# mini3216_V2_0.net
KiCad netlist of a schematic drawn in Altium Designer
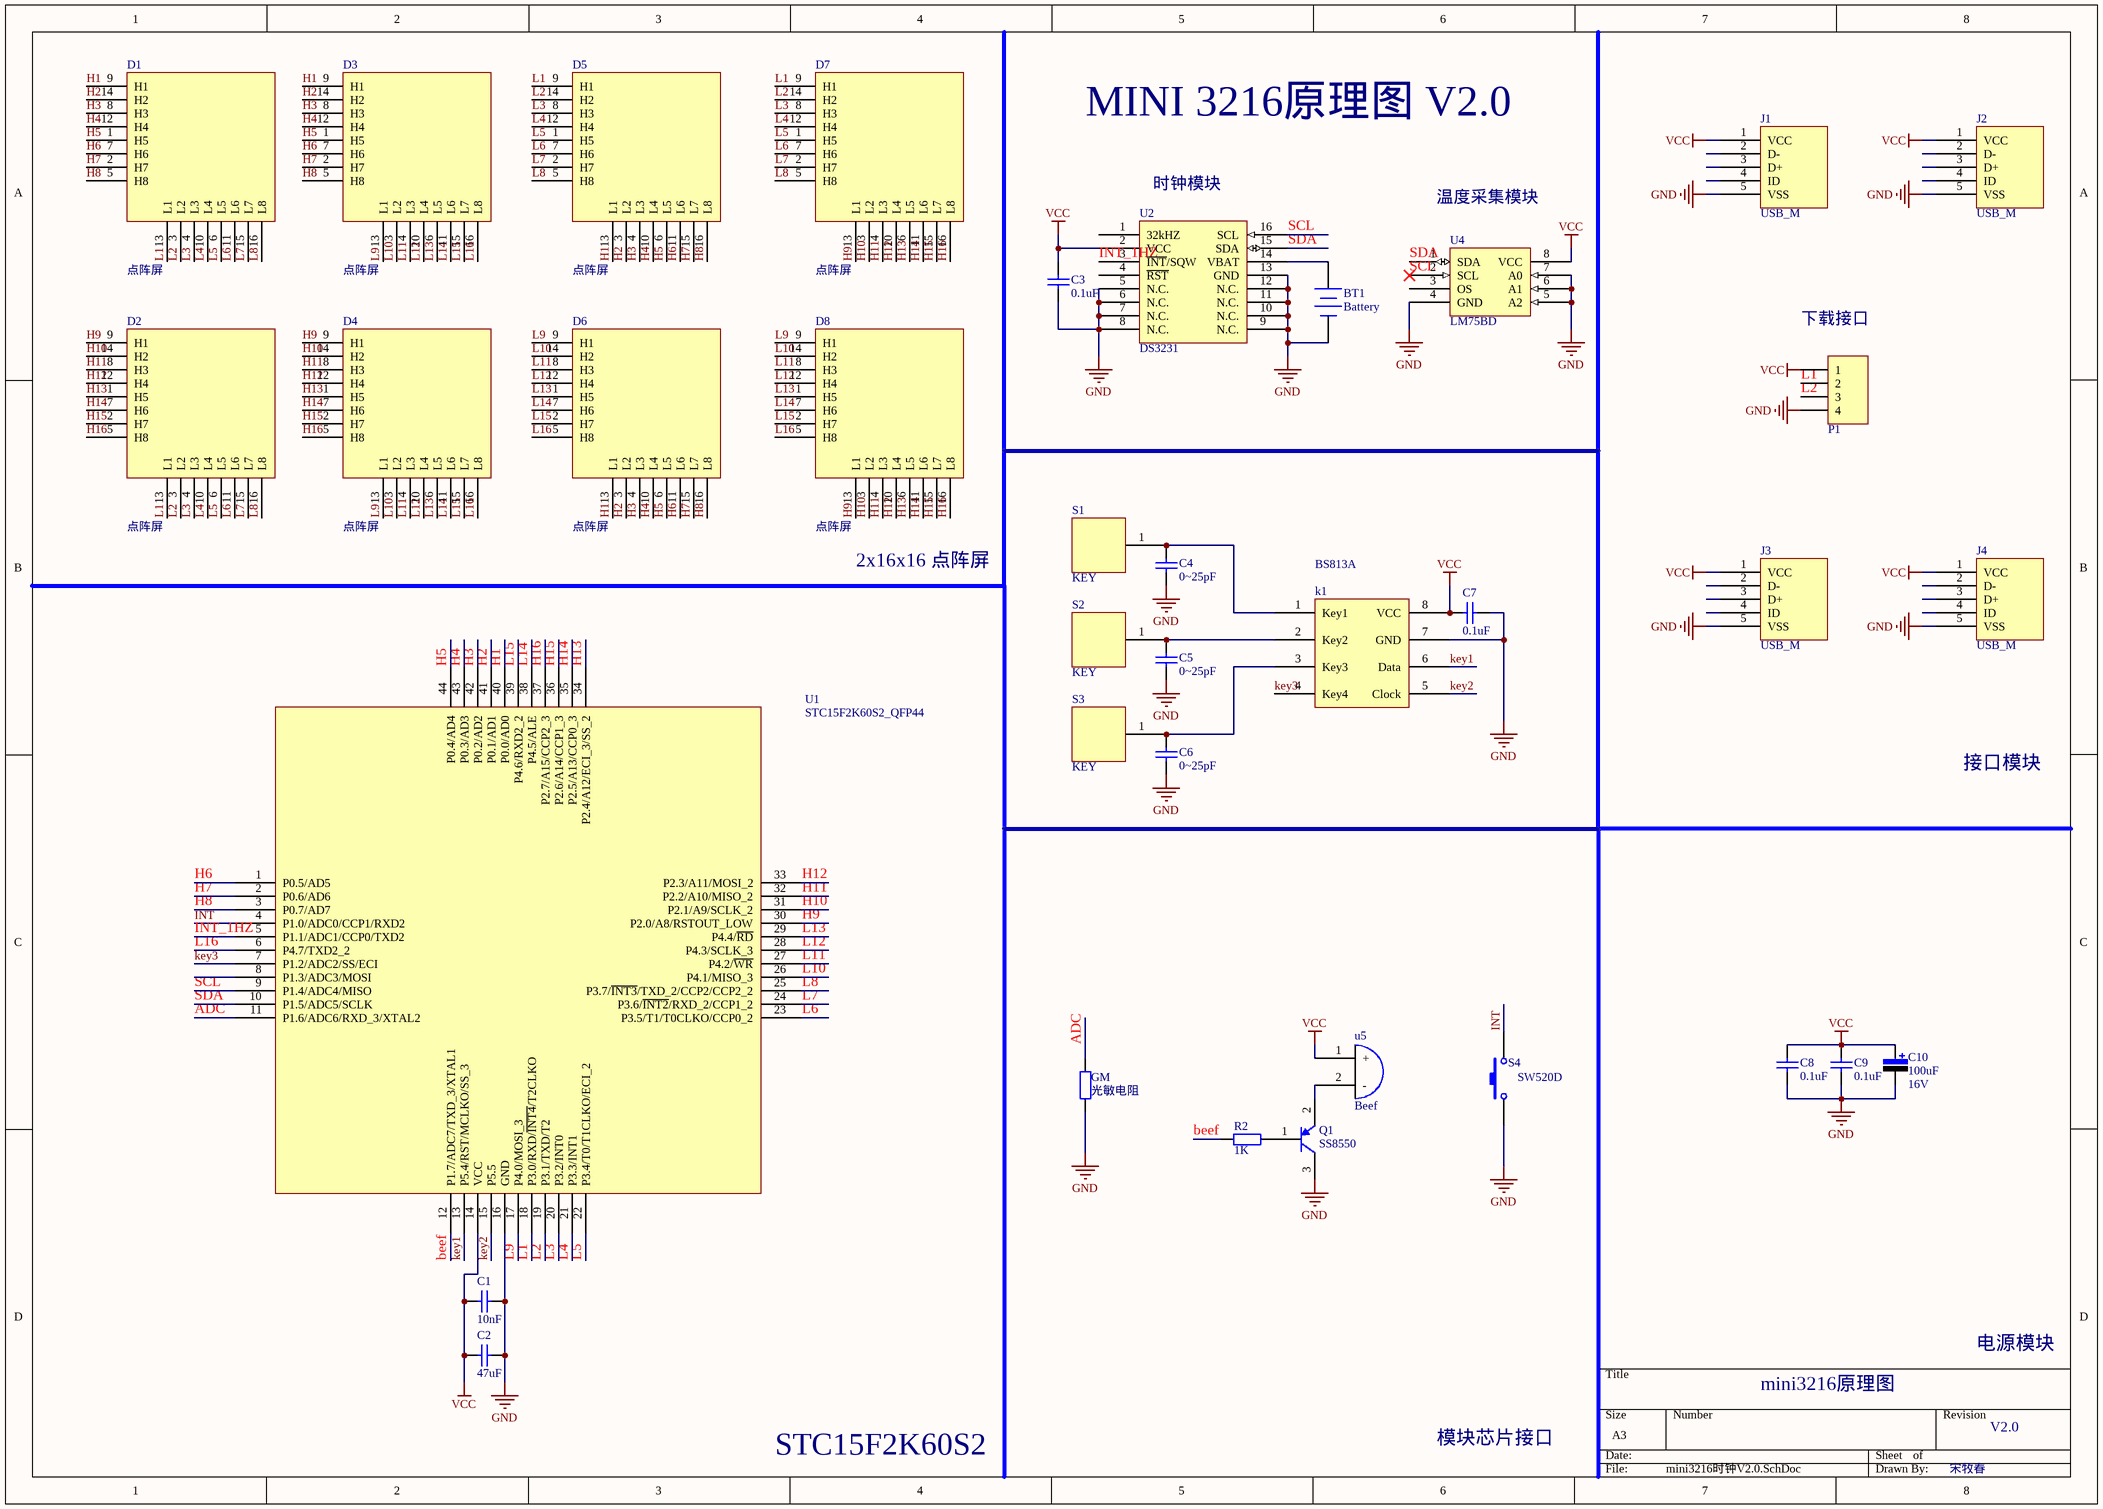
[diagram p0: mini3216时钟V2.0.SchDoc]

(export (version "E")
  (design (tool "Eeschema 10.0.6"))
  (components
    (comp (ref "BT1")
      (value "Battery")
      (footprint "CR1220电池座")
      (description "备份电池")
      (fields (field (name "PUBLISHER") "Altium Limited"))
      (libsource (lib "SMC_Devices") (part "Battery"))
    )
    (comp (ref "C1")
      (value "10nF")
      (footprint "C-RAD-0805")
      (description "无极性电容")
      (fields (field (name "Comment") "Cap") (field (name "PUBLISHER") "Altium Limited"))
      (libsource (lib "SMC_Devices") (part "Cap"))
    )
    (comp (ref "C2")
      (value "47uF")
      (footprint "1206(3216)")
      (description "无极性电容")
      (fields (field (name "Comment") "Cap") (field (name "PUBLISHER") "Altium Limited"))
      (libsource (lib "SMC_Devices") (part "Cap"))
    )
    (comp (ref "C3")
      (value "0.1uF")
      (footprint "C-RAD-0805")
      (description "无极性电容")
      (fields (field (name "Comment") "Cap") (field (name "PUBLISHER") "Altium Limited"))
      (libsource (lib "SMC_Devices") (part "Cap"))
    )
    (comp (ref "C4")
      (value "0~25pF")
      (footprint "C-RAD-0805")
      (description "无极性电容")
      (fields (field (name "Comment") "Cap") (field (name "PUBLISHER") "Altium Limited"))
      (libsource (lib "SMC_Devices") (part "Cap"))
    )
    (comp (ref "C5")
      (value "0~25pF")
      (footprint "C-RAD-0805")
      (description "无极性电容")
      (fields (field (name "Comment") "Cap") (field (name "PUBLISHER") "Altium Limited"))
      (libsource (lib "SMC_Devices") (part "Cap"))
    )
    (comp (ref "C6")
      (value "0~25pF")
      (footprint "C-RAD-0805")
      (description "无极性电容")
      (fields (field (name "Comment") "Cap") (field (name "PUBLISHER") "Altium Limited"))
      (libsource (lib "SMC_Devices") (part "Cap"))
    )
    (comp (ref "C7")
      (value "0.1uF")
      (footprint "C-RAD-0805")
      (description "无极性电容")
      (fields (field (name "Comment") "Cap") (field (name "PUBLISHER") "Altium Limited"))
      (libsource (lib "SMC_Devices") (part "Cap"))
    )
    (comp (ref "C8")
      (value "0.1uF")
      (footprint "C-RAD-0805")
      (description "无极性电容")
      (fields (field (name "Comment") "Cap") (field (name "PUBLISHER") "Altium Limited"))
      (libsource (lib "SMC_Devices") (part "Cap"))
    )
    (comp (ref "C9")
      (value "0.1uF")
      (footprint "C-RAD-0805")
      (description "无极性电容")
      (fields (field (name "Comment") "Cap") (field (name "PUBLISHER") "Altium Limited"))
      (libsource (lib "SMC_Devices") (part "Cap"))
    )
    (comp (ref "C10")
      (value "100uF")
      (footprint "CAP-3528")
      (description "极性电解电容")
      (fields
        (field (name "VOL") "16V")
        (field (name "Comment") "Cap Pol")
        (field (name "PUBLISHER") "Altium Limited")
      )
      (libsource (lib "SMC_Devices") (part "Cap Pol"))
    )
    (comp (ref "D1") (value "点阵屏") (footprint "LED_点阵1088") (libsource (lib "mini3216") (part "LED_点阵屏8x8")))
    (comp (ref "D2") (value "点阵屏") (footprint "LED_点阵1088") (libsource (lib "mini3216") (part "LED_点阵屏8x8")))
    (comp (ref "D3") (value "点阵屏") (footprint "LED_点阵1088") (libsource (lib "mini3216") (part "LED_点阵屏8x8")))
    (comp (ref "D4") (value "点阵屏") (footprint "LED_点阵1088") (libsource (lib "mini3216") (part "LED_点阵屏8x8")))
    (comp (ref "D5") (value "点阵屏") (footprint "LED_点阵1088") (libsource (lib "mini3216") (part "LED_点阵屏8x8")))
    (comp (ref "D6") (value "点阵屏") (footprint "LED_点阵1088") (libsource (lib "mini3216") (part "LED_点阵屏8x8")))
    (comp (ref "D7") (value "点阵屏") (footprint "LED_点阵1088") (libsource (lib "mini3216") (part "LED_点阵屏8x8")))
    (comp (ref "D8") (value "点阵屏") (footprint "LED_点阵1088") (libsource (lib "mini3216") (part "LED_点阵屏8x8")))
    (comp (ref "GM")
      (value "光敏电阻")
      (footprint "光敏电阻")
      (description "贴片电阻")
      (fields (field (name "Comment") "Res1") (field (name "PUBLISHER") "Altium Limited"))
      (libsource (lib "SMC_Devices") (part "Res1"))
    )
    (comp (ref "J1")
      (value "USB_M")
      (footprint "USB_MICRO")
      (description "MicroUSB接口")
      (libsource (lib "SMC_Devices") (part "USB_M"))
    )
    (comp (ref "J2")
      (value "USB_M")
      (footprint "USB_MICRO")
      (description "MicroUSB接口")
      (libsource (lib "SMC_Devices") (part "USB_M"))
    )
    (comp (ref "J3")
      (value "USB_M")
      (footprint "USB_MICRO")
      (description "MicroUSB接口")
      (libsource (lib "SMC_Devices") (part "USB_M"))
    )
    (comp (ref "J4")
      (value "USB_M")
      (footprint "USB_MICRO")
      (description "MicroUSB接口")
      (libsource (lib "SMC_Devices") (part "USB_M"))
    )
    (comp (ref "k1") (value "BS813A") (footprint "SOP8") (libsource (lib "mini3216") (part "BS814A-2触摸按键")))
    (comp (ref "P1")
      (value "Header 4")
      (footprint "HDR4X1_A")
      (description "接插件")
      (fields (field (name "PUBLISHER") "Altium Limited"))
      (libsource (lib "SMC_Devices") (part "Header 4"))
    )
    (comp (ref "Q1")
      (value "SS8550")
      (footprint "SOT-23")
      (description "PNP贴片三极管")
      (fields (field (name "PUBLISHER") "Altium Limited"))
      (libsource (lib "SMC_Devices") (part "SS8550"))
    )
    (comp (ref "R2")
      (value "1K")
      (footprint "0805-1")
      (description "贴片电阻")
      (fields (field (name "Comment") "Res1") (field (name "PUBLISHER") "Altium Limited"))
      (libsource (lib "") (part "Res1_1"))
    )
    (comp (ref "S1") (value "KEY") (footprint "KEY1") (libsource (lib "mini3216") (part "TouchKEY")))
    (comp (ref "S2") (value "KEY") (footprint "KEY2") (libsource (lib "mini3216") (part "TouchKEY")))
    (comp (ref "S3") (value "KEY") (footprint "KEY3") (libsource (lib "mini3216") (part "TouchKEY")))
    (comp (ref "S4")
      (value "SW520D")
      (footprint "SW_PB2_A1")
      (description "微动开关")
      (fields (field (name "PUBLISHER") "Altium Limited"))
      (libsource (lib "SMC_Devices") (part "SW-PB"))
    )
    (comp (ref "U1")
      (value "STC15F2K60S2_QFP44")
      (footprint "LQFP44")
      (libsource (lib "stcmcu_altium_lib") (part "STC15F2K60S2_QFP44"))
    )
    (comp (ref "U2") (value "DS3231") (footprint "DS3231SN") (libsource (lib "mini3216") (part "DS3231")))
    (comp (ref "U4") (value "LM75BD") (footprint "LM75BD") (libsource (lib "mini3216") (part "LM75BD")))
    (comp (ref "u5") (value "Beef") (footprint "BEEF") (libsource (lib "mini3216") (part "Beef")))
  )
  (nets
    (net (code "1") (name "/ADC") (class "Default")
      (node (ref "GM") (pin "2") (pinfunction "2_2") (pintype "passive"))
      (node (ref "U1") (pin "11") (pinfunction "P1.6/ADC6/RXD_3/XTAL2_11") (pintype "passive"))
    )
    (net (code "2") (name "/H1") (class "Default")
      (node (ref "D1") (pin "9") (pinfunction "H1_9") (pintype "passive"))
      (node (ref "D3") (pin "9") (pinfunction "H1_9") (pintype "passive"))
      (node (ref "D5") (pin "13") (pinfunction "L1_13") (pintype "passive"))
      (node (ref "D6") (pin "13") (pinfunction "L1_13") (pintype "passive"))
      (node (ref "U1") (pin "40") (pinfunction "P0.0/AD0_40") (pintype "passive"))
    )
    (net (code "3") (name "/H2") (class "Default")
      (node (ref "D1") (pin "14") (pinfunction "H2_14") (pintype "passive"))
      (node (ref "D3") (pin "14") (pinfunction "H2_14") (pintype "passive"))
      (node (ref "D5") (pin "3") (pinfunction "L2_3") (pintype "passive"))
      (node (ref "D6") (pin "3") (pinfunction "L2_3") (pintype "passive"))
      (node (ref "U1") (pin "41") (pinfunction "P0.1/AD1_41") (pintype "passive"))
    )
    (net (code "4") (name "/H3") (class "Default")
      (node (ref "D1") (pin "8") (pinfunction "H3_8") (pintype "passive"))
      (node (ref "D3") (pin "8") (pinfunction "H3_8") (pintype "passive"))
      (node (ref "D5") (pin "4") (pinfunction "L3_4") (pintype "passive"))
      (node (ref "D6") (pin "4") (pinfunction "L3_4") (pintype "passive"))
      (node (ref "U1") (pin "42") (pinfunction "P0.2/AD2_42") (pintype "passive"))
    )
    (net (code "5") (name "/H4") (class "Default")
      (node (ref "D1") (pin "12") (pinfunction "H4_12") (pintype "passive"))
      (node (ref "D3") (pin "12") (pinfunction "H4_12") (pintype "passive"))
      (node (ref "D5") (pin "10") (pinfunction "L4_10") (pintype "passive"))
      (node (ref "D6") (pin "10") (pinfunction "L4_10") (pintype "passive"))
      (node (ref "U1") (pin "43") (pinfunction "P0.3/AD3_43") (pintype "passive"))
    )
    (net (code "6") (name "/H5") (class "Default")
      (node (ref "D1") (pin "1") (pinfunction "H5_1") (pintype "passive"))
      (node (ref "D3") (pin "1") (pinfunction "H5_1") (pintype "passive"))
      (node (ref "D5") (pin "6") (pinfunction "L5_6") (pintype "passive"))
      (node (ref "D6") (pin "6") (pinfunction "L5_6") (pintype "passive"))
      (node (ref "U1") (pin "44") (pinfunction "P0.4/AD4_44") (pintype "passive"))
    )
    (net (code "7") (name "/H6") (class "Default")
      (node (ref "D1") (pin "7") (pinfunction "H6_7") (pintype "passive"))
      (node (ref "D3") (pin "7") (pinfunction "H6_7") (pintype "passive"))
      (node (ref "D5") (pin "11") (pinfunction "L6_11") (pintype "passive"))
      (node (ref "D6") (pin "11") (pinfunction "L6_11") (pintype "passive"))
      (node (ref "U1") (pin "1") (pinfunction "P0.5/AD5_1") (pintype "passive"))
    )
    (net (code "8") (name "/H7") (class "Default")
      (node (ref "D1") (pin "2") (pinfunction "H7_2") (pintype "passive"))
      (node (ref "D3") (pin "2") (pinfunction "H7_2") (pintype "passive"))
      (node (ref "D5") (pin "15") (pinfunction "L7_15") (pintype "passive"))
      (node (ref "D6") (pin "15") (pinfunction "L7_15") (pintype "passive"))
      (node (ref "U1") (pin "2") (pinfunction "P0.6/AD6_2") (pintype "passive"))
    )
    (net (code "9") (name "/H8") (class "Default")
      (node (ref "D1") (pin "5") (pinfunction "H8_5") (pintype "passive"))
      (node (ref "D3") (pin "5") (pinfunction "H8_5") (pintype "passive"))
      (node (ref "D5") (pin "16") (pinfunction "L8_16") (pintype "passive"))
      (node (ref "D6") (pin "16") (pinfunction "L8_16") (pintype "passive"))
      (node (ref "U1") (pin "3") (pinfunction "P0.7/AD7_3") (pintype "passive"))
    )
    (net (code "10") (name "/H9") (class "Default")
      (node (ref "D2") (pin "9") (pinfunction "H1_9") (pintype "passive"))
      (node (ref "D4") (pin "9") (pinfunction "H1_9") (pintype "passive"))
      (node (ref "D7") (pin "13") (pinfunction "L1_13") (pintype "passive"))
      (node (ref "D8") (pin "13") (pinfunction "L1_13") (pintype "passive"))
      (node (ref "U1") (pin "30") (pinfunction "P2.0/A8/RSTOUT_LOW_30") (pintype "passive"))
    )
    (net (code "11") (name "/H10") (class "Default")
      (node (ref "D2") (pin "14") (pinfunction "H2_14") (pintype "passive"))
      (node (ref "D4") (pin "14") (pinfunction "H2_14") (pintype "passive"))
      (node (ref "D7") (pin "3") (pinfunction "L2_3") (pintype "passive"))
      (node (ref "D8") (pin "3") (pinfunction "L2_3") (pintype "passive"))
      (node (ref "U1") (pin "31") (pinfunction "P2.1/A9/SCLK_2_31") (pintype "passive"))
    )
    (net (code "12") (name "/H11") (class "Default")
      (node (ref "D2") (pin "8") (pinfunction "H3_8") (pintype "passive"))
      (node (ref "D4") (pin "8") (pinfunction "H3_8") (pintype "passive"))
      (node (ref "D7") (pin "4") (pinfunction "L3_4") (pintype "passive"))
      (node (ref "D8") (pin "4") (pinfunction "L3_4") (pintype "passive"))
      (node (ref "U1") (pin "32") (pinfunction "P2.2/A10/MISO_2_32") (pintype "passive"))
    )
    (net (code "13") (name "/H12") (class "Default")
      (node (ref "D2") (pin "12") (pinfunction "H4_12") (pintype "passive"))
      (node (ref "D4") (pin "12") (pinfunction "H4_12") (pintype "passive"))
      (node (ref "D7") (pin "10") (pinfunction "L4_10") (pintype "passive"))
      (node (ref "D8") (pin "10") (pinfunction "L4_10") (pintype "passive"))
      (node (ref "U1") (pin "33") (pinfunction "P2.3/A11/MOSI_2_33") (pintype "passive"))
    )
    (net (code "14") (name "/H13") (class "Default")
      (node (ref "D2") (pin "1") (pinfunction "H5_1") (pintype "passive"))
      (node (ref "D4") (pin "1") (pinfunction "H5_1") (pintype "passive"))
      (node (ref "D7") (pin "6") (pinfunction "L5_6") (pintype "passive"))
      (node (ref "D8") (pin "6") (pinfunction "L5_6") (pintype "passive"))
      (node (ref "U1") (pin "34") (pinfunction "P2.4/A12/ECI_3/SS_2_34") (pintype "passive"))
    )
    (net (code "15") (name "/H14") (class "Default")
      (node (ref "D2") (pin "7") (pinfunction "H6_7") (pintype "passive"))
      (node (ref "D4") (pin "7") (pinfunction "H6_7") (pintype "passive"))
      (node (ref "D7") (pin "11") (pinfunction "L6_11") (pintype "passive"))
      (node (ref "D8") (pin "11") (pinfunction "L6_11") (pintype "passive"))
      (node (ref "U1") (pin "35") (pinfunction "P2.5/A13/CCP0_3_35") (pintype "passive"))
    )
    (net (code "16") (name "/H15") (class "Default")
      (node (ref "D2") (pin "2") (pinfunction "H7_2") (pintype "passive"))
      (node (ref "D4") (pin "2") (pinfunction "H7_2") (pintype "passive"))
      (node (ref "D7") (pin "15") (pinfunction "L7_15") (pintype "passive"))
      (node (ref "D8") (pin "15") (pinfunction "L7_15") (pintype "passive"))
      (node (ref "U1") (pin "36") (pinfunction "P2.6/A14/CCP1_3_36") (pintype "passive"))
    )
    (net (code "17") (name "/H16") (class "Default")
      (node (ref "D2") (pin "5") (pinfunction "H8_5") (pintype "passive"))
      (node (ref "D4") (pin "5") (pinfunction "H8_5") (pintype "passive"))
      (node (ref "D7") (pin "16") (pinfunction "L8_16") (pintype "passive"))
      (node (ref "D8") (pin "16") (pinfunction "L8_16") (pintype "passive"))
      (node (ref "U1") (pin "37") (pinfunction "P2.7/A15/CCP2_3_37") (pintype "passive"))
    )
    (net (code "18") (name "/INT") (class "Default")
      (node (ref "S4") (pin "2") (pinfunction "2_2") (pintype "passive"))
      (node (ref "U1") (pin "4") (pinfunction "P1.0/ADC0/CCP1/RXD2_4") (pintype "passive"))
    )
    (net (code "19") (name "/INT_1HZ") (class "Default")
      (node (ref "U1") (pin "5") (pinfunction "P1.1/ADC1/CCP0/TXD2_5") (pintype "passive"))
      (node (ref "U2") (pin "3") (pinfunction "~{INT}/SQW_3") (pintype "open_collector"))
    )
    (net (code "20") (name "/L1") (class "Default")
      (node (ref "D1") (pin "13") (pinfunction "L1_13") (pintype "passive"))
      (node (ref "D2") (pin "13") (pinfunction "L1_13") (pintype "passive"))
      (node (ref "D5") (pin "9") (pinfunction "H1_9") (pintype "passive"))
      (node (ref "D7") (pin "9") (pinfunction "H1_9") (pintype "passive"))
      (node (ref "P1") (pin "2") (pinfunction "2_2") (pintype "passive"))
      (node (ref "U1") (pin "18") (pinfunction "P3.0/RXD/~{INT4}/T2CLKO_18") (pintype "passive"))
    )
    (net (code "21") (name "/L2") (class "Default")
      (node (ref "D1") (pin "3") (pinfunction "L2_3") (pintype "passive"))
      (node (ref "D2") (pin "3") (pinfunction "L2_3") (pintype "passive"))
      (node (ref "D5") (pin "14") (pinfunction "H2_14") (pintype "passive"))
      (node (ref "D7") (pin "14") (pinfunction "H2_14") (pintype "passive"))
      (node (ref "P1") (pin "3") (pinfunction "3_3") (pintype "passive"))
      (node (ref "U1") (pin "19") (pinfunction "P3.1/TXD/T2_19") (pintype "passive"))
    )
    (net (code "22") (name "/L3") (class "Default")
      (node (ref "D1") (pin "4") (pinfunction "L3_4") (pintype "passive"))
      (node (ref "D2") (pin "4") (pinfunction "L3_4") (pintype "passive"))
      (node (ref "D5") (pin "8") (pinfunction "H3_8") (pintype "passive"))
      (node (ref "D7") (pin "8") (pinfunction "H3_8") (pintype "passive"))
      (node (ref "U1") (pin "20") (pinfunction "P3.2/INT0_20") (pintype "passive"))
    )
    (net (code "23") (name "/L4") (class "Default")
      (node (ref "D1") (pin "10") (pinfunction "L4_10") (pintype "passive"))
      (node (ref "D2") (pin "10") (pinfunction "L4_10") (pintype "passive"))
      (node (ref "D5") (pin "12") (pinfunction "H4_12") (pintype "passive"))
      (node (ref "D7") (pin "12") (pinfunction "H4_12") (pintype "passive"))
      (node (ref "U1") (pin "21") (pinfunction "P3.3/INT1_21") (pintype "passive"))
    )
    (net (code "24") (name "/L5") (class "Default")
      (node (ref "D1") (pin "6") (pinfunction "L5_6") (pintype "passive"))
      (node (ref "D2") (pin "6") (pinfunction "L5_6") (pintype "passive"))
      (node (ref "D5") (pin "1") (pinfunction "H5_1") (pintype "passive"))
      (node (ref "D7") (pin "1") (pinfunction "H5_1") (pintype "passive"))
      (node (ref "U1") (pin "22") (pinfunction "P3.4/T0/T1CLKO/ECI_2_22") (pintype "passive"))
    )
    (net (code "25") (name "/L6") (class "Default")
      (node (ref "D1") (pin "11") (pinfunction "L6_11") (pintype "passive"))
      (node (ref "D2") (pin "11") (pinfunction "L6_11") (pintype "passive"))
      (node (ref "D5") (pin "7") (pinfunction "H6_7") (pintype "passive"))
      (node (ref "D7") (pin "7") (pinfunction "H6_7") (pintype "passive"))
      (node (ref "U1") (pin "23") (pinfunction "P3.5/T1/T0CLKO/CCP0_2_23") (pintype "passive"))
    )
    (net (code "26") (name "/L7") (class "Default")
      (node (ref "D1") (pin "15") (pinfunction "L7_15") (pintype "passive"))
      (node (ref "D2") (pin "15") (pinfunction "L7_15") (pintype "passive"))
      (node (ref "D5") (pin "2") (pinfunction "H7_2") (pintype "passive"))
      (node (ref "D7") (pin "2") (pinfunction "H7_2") (pintype "passive"))
      (node (ref "U1") (pin "24") (pinfunction "P3.6/~{INT2}/RXD_2/CCP1_2_24") (pintype "passive"))
    )
    (net (code "27") (name "/L8") (class "Default")
      (node (ref "D1") (pin "16") (pinfunction "L8_16") (pintype "passive"))
      (node (ref "D2") (pin "16") (pinfunction "L8_16") (pintype "passive"))
      (node (ref "D5") (pin "5") (pinfunction "H8_5") (pintype "passive"))
      (node (ref "D7") (pin "5") (pinfunction "H8_5") (pintype "passive"))
      (node (ref "U1") (pin "25") (pinfunction "P3.7/~{INT3}/TXD_2/CCP2/CCP2_2_25") (pintype "passive"))
    )
    (net (code "28") (name "/L9") (class "Default")
      (node (ref "D3") (pin "13") (pinfunction "L1_13") (pintype "passive"))
      (node (ref "D4") (pin "13") (pinfunction "L1_13") (pintype "passive"))
      (node (ref "D6") (pin "9") (pinfunction "H1_9") (pintype "passive"))
      (node (ref "D8") (pin "9") (pinfunction "H1_9") (pintype "passive"))
      (node (ref "U1") (pin "17") (pinfunction "P4.0/MOSI_3_17") (pintype "passive"))
    )
    (net (code "29") (name "/L10") (class "Default")
      (node (ref "D3") (pin "3") (pinfunction "L2_3") (pintype "passive"))
      (node (ref "D4") (pin "3") (pinfunction "L2_3") (pintype "passive"))
      (node (ref "D6") (pin "14") (pinfunction "H2_14") (pintype "passive"))
      (node (ref "D8") (pin "14") (pinfunction "H2_14") (pintype "passive"))
      (node (ref "U1") (pin "26") (pinfunction "P4.1/MISO_3_26") (pintype "passive"))
    )
    (net (code "30") (name "/L11") (class "Default")
      (node (ref "D3") (pin "4") (pinfunction "L3_4") (pintype "passive"))
      (node (ref "D4") (pin "4") (pinfunction "L3_4") (pintype "passive"))
      (node (ref "D6") (pin "8") (pinfunction "H3_8") (pintype "passive"))
      (node (ref "D8") (pin "8") (pinfunction "H3_8") (pintype "passive"))
      (node (ref "U1") (pin "27") (pinfunction "P4.2/~{WR}_27") (pintype "passive"))
    )
    (net (code "31") (name "/L12") (class "Default")
      (node (ref "D3") (pin "10") (pinfunction "L4_10") (pintype "passive"))
      (node (ref "D4") (pin "10") (pinfunction "L4_10") (pintype "passive"))
      (node (ref "D6") (pin "12") (pinfunction "H4_12") (pintype "passive"))
      (node (ref "D8") (pin "12") (pinfunction "H4_12") (pintype "passive"))
      (node (ref "U1") (pin "28") (pinfunction "P4.3/SCLK_3_28") (pintype "passive"))
    )
    (net (code "32") (name "/L13") (class "Default")
      (node (ref "D3") (pin "6") (pinfunction "L5_6") (pintype "passive"))
      (node (ref "D4") (pin "6") (pinfunction "L5_6") (pintype "passive"))
      (node (ref "D6") (pin "1") (pinfunction "H5_1") (pintype "passive"))
      (node (ref "D8") (pin "1") (pinfunction "H5_1") (pintype "passive"))
      (node (ref "U1") (pin "29") (pinfunction "P4.4/~{RD}_29") (pintype "passive"))
    )
    (net (code "33") (name "/L14") (class "Default")
      (node (ref "D3") (pin "11") (pinfunction "L6_11") (pintype "passive"))
      (node (ref "D4") (pin "11") (pinfunction "L6_11") (pintype "passive"))
      (node (ref "D6") (pin "7") (pinfunction "H6_7") (pintype "passive"))
      (node (ref "D8") (pin "7") (pinfunction "H6_7") (pintype "passive"))
      (node (ref "U1") (pin "38") (pinfunction "P4.5/ALE_38") (pintype "passive"))
    )
    (net (code "34") (name "/L15") (class "Default")
      (node (ref "D3") (pin "15") (pinfunction "L7_15") (pintype "passive"))
      (node (ref "D4") (pin "15") (pinfunction "L7_15") (pintype "passive"))
      (node (ref "D6") (pin "2") (pinfunction "H7_2") (pintype "passive"))
      (node (ref "D8") (pin "2") (pinfunction "H7_2") (pintype "passive"))
      (node (ref "U1") (pin "39") (pinfunction "P4.6/RXD2_2_39") (pintype "passive"))
    )
    (net (code "35") (name "/L16") (class "Default")
      (node (ref "D3") (pin "16") (pinfunction "L8_16") (pintype "passive"))
      (node (ref "D4") (pin "16") (pinfunction "L8_16") (pintype "passive"))
      (node (ref "D6") (pin "5") (pinfunction "H8_5") (pintype "passive"))
      (node (ref "D8") (pin "5") (pinfunction "H8_5") (pintype "passive"))
      (node (ref "U1") (pin "6") (pinfunction "P4.7/TXD2_2_6") (pintype "passive"))
    )
    (net (code "36") (name "/SCL") (class "Default")
      (node (ref "U1") (pin "9") (pinfunction "P1.4/ADC4/MISO_9") (pintype "passive"))
      (node (ref "U2") (pin "16") (pinfunction "SCL_16") (pintype "input"))
      (node (ref "U4") (pin "2") (pinfunction "SCL_2") (pintype "input"))
    )
    (net (code "37") (name "/SDA") (class "Default")
      (node (ref "U1") (pin "10") (pinfunction "P1.5/ADC5/SCLK_10") (pintype "passive"))
      (node (ref "U2") (pin "15") (pinfunction "SDA_15") (pintype "bidirectional"))
      (node (ref "U4") (pin "1") (pinfunction "SDA_1") (pintype "bidirectional"))
    )
    (net (code "38") (name "/beef") (class "Default")
      (node (ref "R2") (pin "1") (pinfunction "1_1") (pintype "passive"))
      (node (ref "U1") (pin "12") (pinfunction "P1.7/ADC7/TXD_3/XTAL1_12") (pintype "passive"))
    )
    (net (code "39") (name "/key1") (class "Default")
      (node (ref "U1") (pin "13") (pinfunction "P5.4/RST/MCLKO/SS_3_13") (pintype "passive"))
      (node (ref "k1") (pin "6") (pinfunction "Data_6") (pintype "passive"))
    )
    (net (code "40") (name "/key2") (class "Default")
      (node (ref "U1") (pin "15") (pinfunction "P5.5_15") (pintype "passive"))
      (node (ref "k1") (pin "5") (pinfunction "Clock_5") (pintype "passive"))
    )
    (net (code "41") (name "/key3") (class "Default")
      (node (ref "U1") (pin "7") (pinfunction "P1.2/ADC2/SS/ECI_7") (pintype "passive"))
      (node (ref "k1") (pin "4") (pinfunction "Key4_4") (pintype "passive"))
    )
    (net (code "42") (name "GND") (class "Default")
      (node (ref "BT1") (pin "2") (pinfunction "-_2") (pintype "passive"))
      (node (ref "C1") (pin "2") (pinfunction "2_2") (pintype "passive"))
      (node (ref "C10") (pin "2") (pinfunction "2_2") (pintype "passive"))
      (node (ref "C2") (pin "2") (pinfunction "2_2") (pintype "passive"))
      (node (ref "C3") (pin "1") (pinfunction "1_1") (pintype "passive"))
      (node (ref "C4") (pin "1") (pinfunction "1_1") (pintype "passive"))
      (node (ref "C5") (pin "1") (pinfunction "1_1") (pintype "passive"))
      (node (ref "C6") (pin "1") (pinfunction "1_1") (pintype "passive"))
      (node (ref "C7") (pin "2") (pinfunction "2_2") (pintype "passive"))
      (node (ref "C8") (pin "1") (pinfunction "1_1") (pintype "passive"))
      (node (ref "C9") (pin "1") (pinfunction "1_1") (pintype "passive"))
      (node (ref "GM") (pin "1") (pinfunction "1_1") (pintype "passive"))
      (node (ref "J1") (pin "5") (pinfunction "VSS_5") (pintype "passive"))
      (node (ref "J2") (pin "5") (pinfunction "VSS_5") (pintype "passive"))
      (node (ref "J3") (pin "5") (pinfunction "VSS_5") (pintype "passive"))
      (node (ref "J4") (pin "5") (pinfunction "VSS_5") (pintype "passive"))
      (node (ref "P1") (pin "4") (pinfunction "4_4") (pintype "passive"))
      (node (ref "Q1") (pin "3") (pinfunction "C_3") (pintype "passive"))
      (node (ref "S4") (pin "1") (pinfunction "1_1") (pintype "passive"))
      (node (ref "U1") (pin "16") (pinfunction "GND_16") (pintype "passive"))
      (node (ref "U2") (pin "10") (pinfunction "N.C._10") (pintype "passive"))
      (node (ref "U2") (pin "11") (pinfunction "N.C._11") (pintype "passive"))
      (node (ref "U2") (pin "12") (pinfunction "N.C._12") (pintype "passive"))
      (node (ref "U2") (pin "13") (pinfunction "GND_13") (pintype "power_in"))
      (node (ref "U2") (pin "5") (pinfunction "N.C._5") (pintype "passive"))
      (node (ref "U2") (pin "6") (pinfunction "N.C._6") (pintype "passive"))
      (node (ref "U2") (pin "7") (pinfunction "N.C._7") (pintype "passive"))
      (node (ref "U2") (pin "8") (pinfunction "N.C._8") (pintype "passive"))
      (node (ref "U2") (pin "9") (pinfunction "N.C._9") (pintype "passive"))
      (node (ref "U4") (pin "4") (pinfunction "GND_4") (pintype "power_in"))
      (node (ref "U4") (pin "5") (pinfunction "A2_5") (pintype "input"))
      (node (ref "U4") (pin "6") (pinfunction "A1_6") (pintype "input"))
      (node (ref "U4") (pin "7") (pinfunction "A0_7") (pintype "input"))
      (node (ref "k1") (pin "7") (pinfunction "GND_7") (pintype "passive"))
    )
    (net (code "43") (name "Net-(BT1-+)") (class "Default")
      (node (ref "BT1") (pin "1") (pinfunction "+_1") (pintype "passive"))
      (node (ref "U2") (pin "14") (pinfunction "VBAT_14") (pintype "power_in"))
    )
    (net (code "44") (name "Net-(Q1-B)") (class "Default")
      (node (ref "Q1") (pin "1") (pinfunction "B_1") (pintype "passive"))
      (node (ref "R2") (pin "2") (pinfunction "2_2") (pintype "passive"))
    )
    (net (code "45") (name "Net-(Q1-E)") (class "Default")
      (node (ref "Q1") (pin "2") (pinfunction "E_2") (pintype "passive"))
      (node (ref "u5") (pin "2") (pinfunction "-_2") (pintype "passive"))
    )
    (net (code "46") (name "Net-(k1-Key1)") (class "Default")
      (node (ref "C4") (pin "2") (pinfunction "2_2") (pintype "passive"))
      (node (ref "S1") (pin "1") (pinfunction "1_1") (pintype "passive"))
      (node (ref "k1") (pin "1") (pinfunction "Key1_1") (pintype "passive"))
    )
    (net (code "47") (name "Net-(k1-Key2)") (class "Default")
      (node (ref "C5") (pin "2") (pinfunction "2_2") (pintype "passive"))
      (node (ref "S2") (pin "1") (pinfunction "1_1") (pintype "passive"))
      (node (ref "k1") (pin "2") (pinfunction "Key2_2") (pintype "passive"))
    )
    (net (code "48") (name "Net-(k1-Key3)") (class "Default")
      (node (ref "C6") (pin "2") (pinfunction "2_2") (pintype "passive"))
      (node (ref "S3") (pin "1") (pinfunction "1_1") (pintype "passive"))
      (node (ref "k1") (pin "3") (pinfunction "Key3_3") (pintype "passive"))
    )
    (net (code "49") (name "VCC") (class "Default")
      (node (ref "C1") (pin "1") (pinfunction "1_1") (pintype "passive"))
      (node (ref "C10") (pin "1") (pinfunction "1_1") (pintype "passive"))
      (node (ref "C2") (pin "1") (pinfunction "1_1") (pintype "passive"))
      (node (ref "C3") (pin "2") (pinfunction "2_2") (pintype "passive"))
      (node (ref "C7") (pin "1") (pinfunction "1_1") (pintype "passive"))
      (node (ref "C8") (pin "2") (pinfunction "2_2") (pintype "passive"))
      (node (ref "C9") (pin "2") (pinfunction "2_2") (pintype "passive"))
      (node (ref "J1") (pin "1") (pinfunction "VCC_1") (pintype "passive"))
      (node (ref "J2") (pin "1") (pinfunction "VCC_1") (pintype "passive"))
      (node (ref "J3") (pin "1") (pinfunction "VCC_1") (pintype "passive"))
      (node (ref "J4") (pin "1") (pinfunction "VCC_1") (pintype "passive"))
      (node (ref "P1") (pin "1") (pinfunction "1_1") (pintype "passive"))
      (node (ref "U1") (pin "14") (pinfunction "VCC_14") (pintype "passive"))
      (node (ref "U2") (pin "2") (pinfunction "VCC_2") (pintype "power_in"))
      (node (ref "U4") (pin "8") (pinfunction "VCC_8") (pintype "power_in"))
      (node (ref "k1") (pin "8") (pinfunction "VCC_8") (pintype "passive"))
      (node (ref "u5") (pin "1") (pinfunction "+_1") (pintype "power_in"))
    )
    (net (code "50") (name "unconnected-(J1-D+-Pad3)") (class "Default")
      (node (ref "J1") (pin "3") (pinfunction "D+_3") (pintype "passive"))
    )
    (net (code "51") (name "unconnected-(J1-D--Pad2)") (class "Default")
      (node (ref "J1") (pin "2") (pinfunction "D-_2") (pintype "passive"))
    )
    (net (code "52") (name "unconnected-(J1-ID-Pad4)") (class "Default")
      (node (ref "J1") (pin "4") (pinfunction "ID_4") (pintype "passive"))
    )
    (net (code "53") (name "unconnected-(J2-D+-Pad3)") (class "Default")
      (node (ref "J2") (pin "3") (pinfunction "D+_3") (pintype "passive"))
    )
    (net (code "54") (name "unconnected-(J2-D--Pad2)") (class "Default")
      (node (ref "J2") (pin "2") (pinfunction "D-_2") (pintype "passive"))
    )
    (net (code "55") (name "unconnected-(J2-ID-Pad4)") (class "Default")
      (node (ref "J2") (pin "4") (pinfunction "ID_4") (pintype "passive"))
    )
    (net (code "56") (name "unconnected-(J3-D+-Pad3)") (class "Default")
      (node (ref "J3") (pin "3") (pinfunction "D+_3") (pintype "passive"))
    )
    (net (code "57") (name "unconnected-(J3-D--Pad2)") (class "Default")
      (node (ref "J3") (pin "2") (pinfunction "D-_2") (pintype "passive"))
    )
    (net (code "58") (name "unconnected-(J3-ID-Pad4)") (class "Default")
      (node (ref "J3") (pin "4") (pinfunction "ID_4") (pintype "passive"))
    )
    (net (code "59") (name "unconnected-(J4-D+-Pad3)") (class "Default")
      (node (ref "J4") (pin "3") (pinfunction "D+_3") (pintype "passive"))
    )
    (net (code "60") (name "unconnected-(J4-D--Pad2)") (class "Default")
      (node (ref "J4") (pin "2") (pinfunction "D-_2") (pintype "passive"))
    )
    (net (code "61") (name "unconnected-(J4-ID-Pad4)") (class "Default")
      (node (ref "J4") (pin "4") (pinfunction "ID_4") (pintype "passive"))
    )
    (net (code "62") (name "unconnected-(U1-P1.3{slash}ADC3{slash}MOSI-Pad8)") (class "Default")
      (node (ref "U1") (pin "8") (pinfunction "P1.3/ADC3/MOSI_8") (pintype "passive"))
    )
    (net (code "63") (name "unconnected-(U2-32kHZ-Pad1)") (class "Default")
      (node (ref "U2") (pin "1") (pinfunction "32kHZ_1") (pintype "open_collector"))
    )
    (net (code "64") (name "unconnected-(U2-~{RST}-Pad4)") (class "Default")
      (node (ref "U2") (pin "4") (pinfunction "~{RST}_4") (pintype "open_collector"))
    )
    (net (code "65") (name "unconnected-(U4-OS-Pad3)") (class "Default")
      (node (ref "U4") (pin "3") (pinfunction "OS_3") (pintype "open_collector"))
    )
  )
)
